# LowVBoard_02.net
KiCad netlist of a schematic drawn in EAGLE
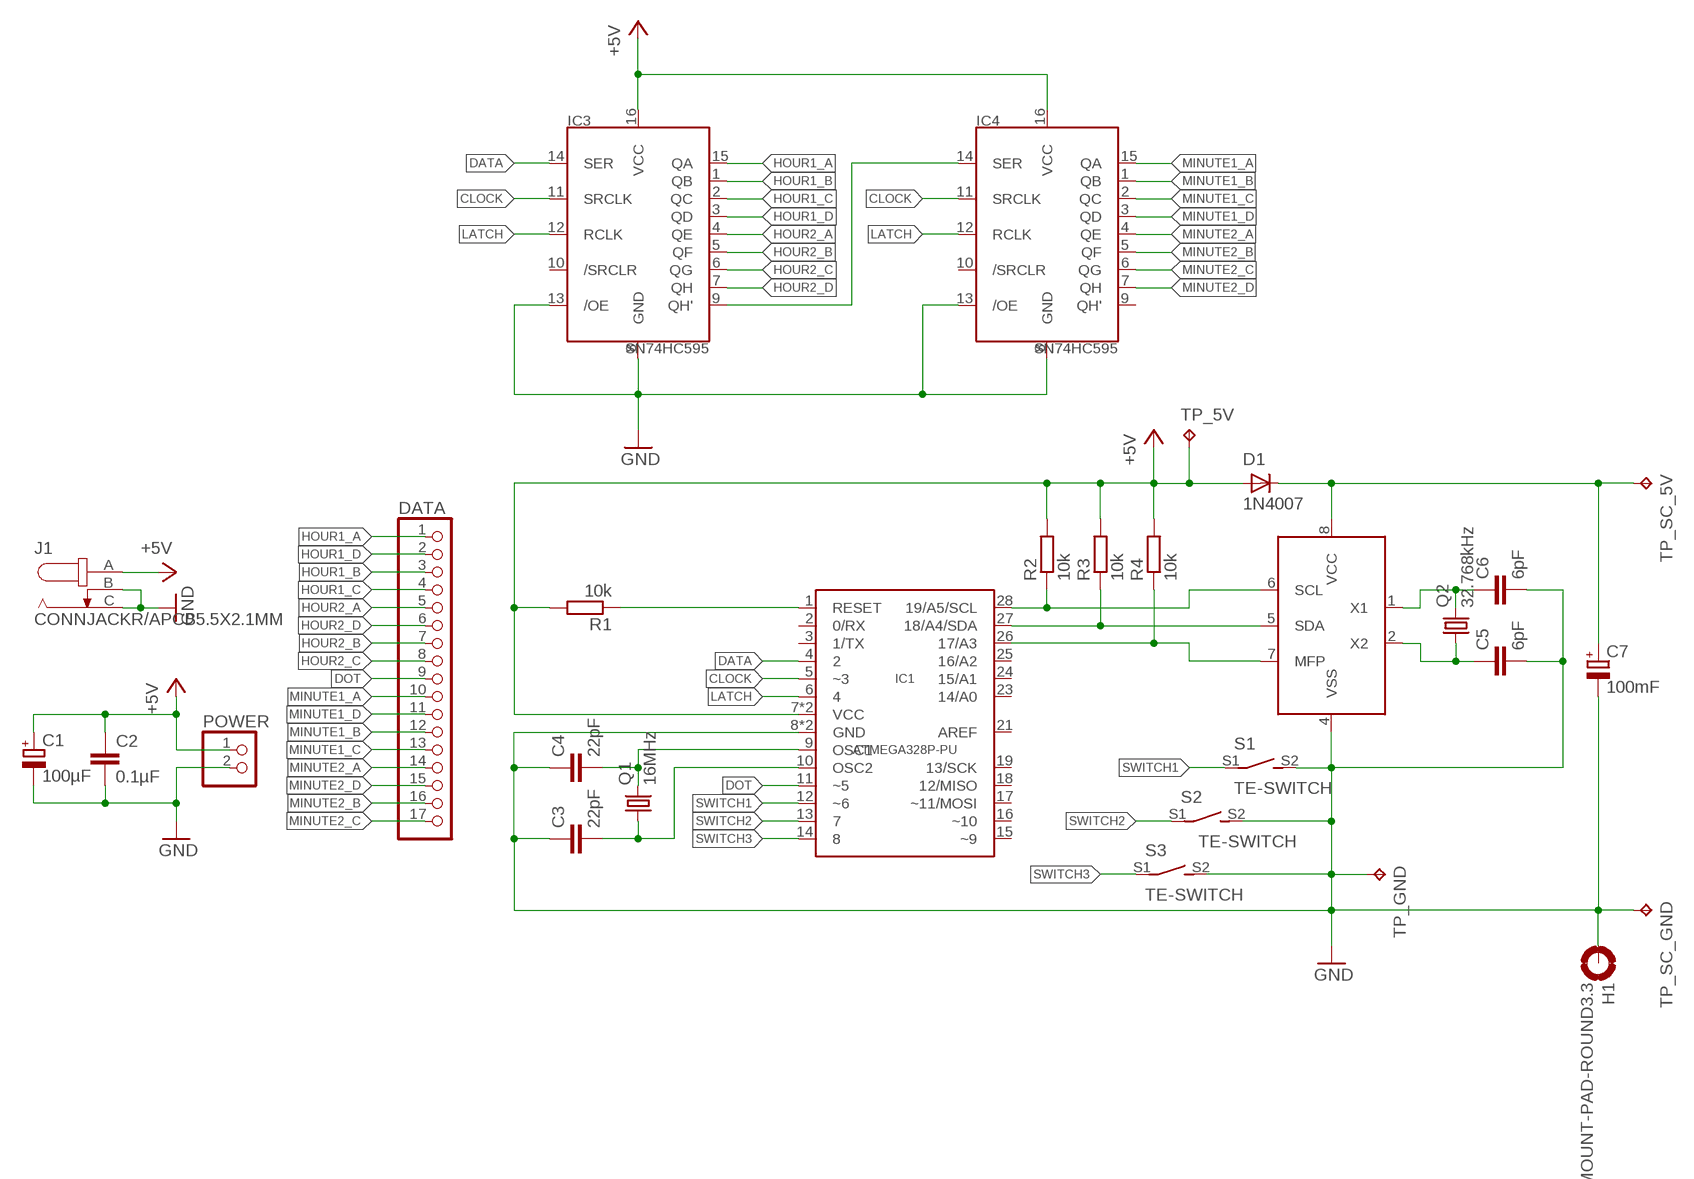
[diagram p0: schematic, sheet 1]

(export (version "E")
  (design (tool "Eeschema 10.0.6"))
  (components
    (comp (ref "C1")
      (value "100µF")
      (footprint "eagle-import:E2-5")
      (libsource (lib "eagle-import") (part "CPOL-EUE2-5"))
    )
    (comp (ref "C2")
      (value "0.1µF")
      (footprint "eagle-import:C025-024X044")
      (libsource (lib "eagle-import") (part "C-EU025-024X044"))
    )
    (comp (ref "C3")
      (value "22pF")
      (footprint "eagle-import:C025-024X044")
      (libsource (lib "eagle-import") (part "C-EU025-024X044"))
    )
    (comp (ref "C4")
      (value "22pF")
      (footprint "eagle-import:C025-024X044")
      (libsource (lib "eagle-import") (part "C-EU025-024X044"))
    )
    (comp (ref "C5")
      (value "6pF")
      (footprint "eagle-import:C025-024X044")
      (libsource (lib "eagle-import") (part "C-EU025-024X044"))
    )
    (comp (ref "C6")
      (value "6pF")
      (footprint "eagle-import:C025-024X044")
      (libsource (lib "eagle-import") (part "C-EU025-024X044"))
    )
    (comp (ref "C7")
      (value "100mF")
      (footprint "eagle-import:SUPERCAP-11.5")
      (libsource (lib "eagle-import") (part "FTW0H104ZF"))
    )
    (comp (ref "D1")
      (value "1N4007")
      (footprint "eagle-import:DO41-7.6")
      (libsource (lib "eagle-import") (part "1N4007"))
    )
    (comp (ref "DATA")
      (value "PINHD-1X17")
      (footprint "eagle-import:1X17")
      (libsource (lib "eagle-import") (part "PINHD-1X17"))
    )
    (comp (ref "H1")
      (value "MOUNT-PAD-ROUND3.3")
      (footprint "eagle-import:3,3-PAD")
      (libsource (lib "eagle-import") (part "MOUNT-PAD-ROUND3.3"))
    )
    (comp (ref "IC1")
      (value "ATMEGA328P-PU")
      (footprint "eagle-import:DIP28")
      (libsource (lib "eagle-import") (part "ATMEGA328P-PU"))
    )
    (comp (ref "IC2")
      (value "MCP7940M")
      (footprint "eagle-import:DIL8")
      (libsource (lib "eagle-import") (part "MCP7940M-I/P"))
    )
    (comp (ref "IC3")
      (value "SN74HC595")
      (footprint "eagle-import:DIL16")
      (libsource (lib "eagle-import") (part "SN74HC595"))
    )
    (comp (ref "IC4")
      (value "SN74HC595")
      (footprint "eagle-import:DIL16")
      (libsource (lib "eagle-import") (part "SN74HC595"))
    )
    (comp (ref "J1")
      (value "CONNJACKR/APCB5.5X2.1MM")
      (footprint "eagle-import:CONNJACKR_APCB5.5X2.1MM")
      (libsource (lib "eagle-import") (part "CONNJACKR/APCB5.5X2.1MM"))
    )
    (comp (ref "POWER")
      (value "PINHD-1X2")
      (footprint "eagle-import:1X02")
      (libsource (lib "eagle-import") (part "PINHD-1X2"))
    )
    (comp (ref "Q1")
      (value "16MHz")
      (footprint "eagle-import:HC49_S")
      (libsource (lib "eagle-import") (part "CRYSTALHC49S"))
    )
    (comp (ref "Q2")
      (value "32.768kHz")
      (footprint "eagle-import:CFS-206")
      (libsource (lib "eagle-import") (part "CFS-206"))
    )
    (comp (ref "R1")
      (value "10k")
      (footprint "eagle-import:0207_7")
      (libsource (lib "eagle-import") (part "R-EU_0207/7"))
    )
    (comp (ref "R2")
      (value "10k")
      (footprint "eagle-import:0207_7")
      (libsource (lib "eagle-import") (part "R-EU_0207/7"))
    )
    (comp (ref "R3")
      (value "10k")
      (footprint "eagle-import:0207_7")
      (libsource (lib "eagle-import") (part "R-EU_0207/7"))
    )
    (comp (ref "R4")
      (value "10k")
      (footprint "eagle-import:0207_7")
      (libsource (lib "eagle-import") (part "R-EU_0207/7"))
    )
    (comp (ref "S1")
      (value "TE-SWITCH")
      (footprint "eagle-import:TE-SWITCH")
      (libsource (lib "eagle-import") (part "TE-SWITCH"))
    )
    (comp (ref "S2")
      (value "TE-SWITCH")
      (footprint "eagle-import:TE-SWITCH")
      (libsource (lib "eagle-import") (part "TE-SWITCH"))
    )
    (comp (ref "S3")
      (value "TE-SWITCH")
      (footprint "eagle-import:TE-SWITCH")
      (libsource (lib "eagle-import") (part "TE-SWITCH"))
    )
    (comp (ref "TP_5V")
      (value "TPPAD1-13")
      (footprint "eagle-import:P1-13")
      (libsource (lib "eagle-import") (part "TPPAD1-13"))
    )
    (comp (ref "TP_GND")
      (value "TPPAD1-13")
      (footprint "eagle-import:P1-13")
      (libsource (lib "eagle-import") (part "TPPAD1-13"))
    )
    (comp (ref "TP_SC_5V")
      (value "TPPAD1-13")
      (footprint "eagle-import:P1-13")
      (libsource (lib "eagle-import") (part "TPPAD1-13"))
    )
    (comp (ref "TP_SC_GND")
      (value "TPPAD1-13")
      (footprint "eagle-import:P1-13")
      (libsource (lib "eagle-import") (part "TPPAD1-13"))
    )
  )
  (nets
    (net (code "1") (name "+5V") (class "Default")
      (node (ref "C1") (pin "+") (pinfunction "+_+") (pintype "passive"))
      (node (ref "C2") (pin "1") (pinfunction "1_1") (pintype "passive"))
      (node (ref "D1") (pin "A") (pinfunction "A_A") (pintype "passive"))
      (node (ref "IC1") (pin "20") (pinfunction "VCC_20") (pintype "bidirectional"))
      (node (ref "IC1") (pin "7") (pinfunction "VCC_7") (pintype "bidirectional"))
      (node (ref "IC3") (pin "16") (pinfunction "VCC_16") (pintype "bidirectional"))
      (node (ref "IC4") (pin "16") (pinfunction "VCC_16") (pintype "bidirectional"))
      (node (ref "J1") (pin "A") (pinfunction "A_A") (pintype "passive"))
      (node (ref "POWER") (pin "1") (pinfunction "1_1") (pintype "passive"))
      (node (ref "R1") (pin "2") (pinfunction "2_2") (pintype "passive"))
      (node (ref "R2") (pin "2") (pinfunction "2_2") (pintype "passive"))
      (node (ref "R3") (pin "2") (pinfunction "2_2") (pintype "passive"))
      (node (ref "R4") (pin "2") (pinfunction "2_2") (pintype "passive"))
      (node (ref "TP_5V") (pin "TP") (pinfunction "TP_TP") (pintype "input"))
    )
    (net (code "2") (name "CLOCK") (class "Default")
      (node (ref "IC1") (pin "5") (pinfunction "~{3}_5") (pintype "bidirectional"))
      (node (ref "IC3") (pin "11") (pinfunction "SRCLK_11") (pintype "bidirectional"))
      (node (ref "IC4") (pin "11") (pinfunction "SRCLK_11") (pintype "bidirectional"))
    )
    (net (code "3") (name "DATA") (class "Default")
      (node (ref "IC1") (pin "4") (pinfunction "2_4") (pintype "bidirectional"))
      (node (ref "IC3") (pin "14") (pinfunction "SER_14") (pintype "bidirectional"))
    )
    (net (code "4") (name "DOT") (class "Default")
      (node (ref "DATA") (pin "9") (pinfunction "9_9") (pintype "passive"))
      (node (ref "IC1") (pin "11") (pinfunction "~{5}_11") (pintype "bidirectional"))
    )
    (net (code "5") (name "GND") (class "Default")
      (node (ref "C1") (pin "-") (pinfunction "-_-") (pintype "passive"))
      (node (ref "C2") (pin "2") (pinfunction "2_2") (pintype "passive"))
      (node (ref "C3") (pin "1") (pinfunction "1_1") (pintype "passive"))
      (node (ref "C4") (pin "1") (pinfunction "1_1") (pintype "passive"))
      (node (ref "C5") (pin "2") (pinfunction "2_2") (pintype "passive"))
      (node (ref "C6") (pin "2") (pinfunction "2_2") (pintype "passive"))
      (node (ref "C7") (pin "-") (pinfunction "-_-") (pintype "passive"))
      (node (ref "H1") (pin "B3,3") (pinfunction "MOUNT_B3,3") (pintype "passive"))
      (node (ref "IC1") (pin "22") (pinfunction "GND_22") (pintype "bidirectional"))
      (node (ref "IC1") (pin "8") (pinfunction "GND_8") (pintype "bidirectional"))
      (node (ref "IC2") (pin "4") (pinfunction "VSS_4") (pintype "bidirectional"))
      (node (ref "IC3") (pin "13") (pinfunction "/OE_13") (pintype "bidirectional"))
      (node (ref "IC3") (pin "8") (pinfunction "GND_8") (pintype "bidirectional"))
      (node (ref "IC4") (pin "13") (pinfunction "/OE_13") (pintype "bidirectional"))
      (node (ref "IC4") (pin "8") (pinfunction "GND_8") (pintype "bidirectional"))
      (node (ref "J1") (pin "B") (pinfunction "B_B") (pintype "passive"))
      (node (ref "J1") (pin "C") (pinfunction "C_C") (pintype "passive"))
      (node (ref "POWER") (pin "2") (pinfunction "2_2") (pintype "passive"))
      (node (ref "S1") (pin "S2") (pinfunction "S_S2") (pintype "passive"))
      (node (ref "S2") (pin "S2") (pinfunction "S_S2") (pintype "passive"))
      (node (ref "S3") (pin "S2") (pinfunction "S_S2") (pintype "passive"))
      (node (ref "TP_GND") (pin "TP") (pinfunction "TP_TP") (pintype "input"))
      (node (ref "TP_SC_GND") (pin "TP") (pinfunction "TP_TP") (pintype "input"))
    )
    (net (code "6") (name "HOUR1_A") (class "Default")
      (node (ref "DATA") (pin "1") (pinfunction "1_1") (pintype "passive"))
      (node (ref "IC3") (pin "15") (pinfunction "QA_15") (pintype "bidirectional"))
    )
    (net (code "7") (name "HOUR1_B") (class "Default")
      (node (ref "DATA") (pin "3") (pinfunction "3_3") (pintype "passive"))
      (node (ref "IC3") (pin "1") (pinfunction "QB_1") (pintype "bidirectional"))
    )
    (net (code "8") (name "HOUR1_C") (class "Default")
      (node (ref "DATA") (pin "4") (pinfunction "4_4") (pintype "passive"))
      (node (ref "IC3") (pin "2") (pinfunction "QC_2") (pintype "bidirectional"))
    )
    (net (code "9") (name "HOUR1_D") (class "Default")
      (node (ref "DATA") (pin "2") (pinfunction "2_2") (pintype "passive"))
      (node (ref "IC3") (pin "3") (pinfunction "QD_3") (pintype "bidirectional"))
    )
    (net (code "10") (name "HOUR2_A") (class "Default")
      (node (ref "DATA") (pin "5") (pinfunction "5_5") (pintype "passive"))
      (node (ref "IC3") (pin "4") (pinfunction "QE_4") (pintype "bidirectional"))
    )
    (net (code "11") (name "HOUR2_B") (class "Default")
      (node (ref "DATA") (pin "7") (pinfunction "7_7") (pintype "passive"))
      (node (ref "IC3") (pin "5") (pinfunction "QF_5") (pintype "bidirectional"))
    )
    (net (code "12") (name "HOUR2_C") (class "Default")
      (node (ref "DATA") (pin "8") (pinfunction "8_8") (pintype "passive"))
      (node (ref "IC3") (pin "6") (pinfunction "QG_6") (pintype "bidirectional"))
    )
    (net (code "13") (name "HOUR2_D") (class "Default")
      (node (ref "DATA") (pin "6") (pinfunction "6_6") (pintype "passive"))
      (node (ref "IC3") (pin "7") (pinfunction "QH_7") (pintype "bidirectional"))
    )
    (net (code "14") (name "LATCH") (class "Default")
      (node (ref "IC1") (pin "6") (pinfunction "4_6") (pintype "bidirectional"))
      (node (ref "IC3") (pin "12") (pinfunction "RCLK_12") (pintype "bidirectional"))
      (node (ref "IC4") (pin "12") (pinfunction "RCLK_12") (pintype "bidirectional"))
    )
    (net (code "15") (name "MINUTE1_A") (class "Default")
      (node (ref "DATA") (pin "10") (pinfunction "10_10") (pintype "passive"))
      (node (ref "IC4") (pin "15") (pinfunction "QA_15") (pintype "bidirectional"))
    )
    (net (code "16") (name "MINUTE1_B") (class "Default")
      (node (ref "DATA") (pin "12") (pinfunction "12_12") (pintype "passive"))
      (node (ref "IC4") (pin "1") (pinfunction "QB_1") (pintype "bidirectional"))
    )
    (net (code "17") (name "MINUTE1_C") (class "Default")
      (node (ref "DATA") (pin "13") (pinfunction "13_13") (pintype "passive"))
      (node (ref "IC4") (pin "2") (pinfunction "QC_2") (pintype "bidirectional"))
    )
    (net (code "18") (name "MINUTE1_D") (class "Default")
      (node (ref "DATA") (pin "11") (pinfunction "11_11") (pintype "passive"))
      (node (ref "IC4") (pin "3") (pinfunction "QD_3") (pintype "bidirectional"))
    )
    (net (code "19") (name "MINUTE2_A") (class "Default")
      (node (ref "DATA") (pin "14") (pinfunction "14_14") (pintype "passive"))
      (node (ref "IC4") (pin "4") (pinfunction "QE_4") (pintype "bidirectional"))
    )
    (net (code "20") (name "MINUTE2_B") (class "Default")
      (node (ref "DATA") (pin "16") (pinfunction "16_16") (pintype "passive"))
      (node (ref "IC4") (pin "5") (pinfunction "QF_5") (pintype "bidirectional"))
    )
    (net (code "21") (name "MINUTE2_C") (class "Default")
      (node (ref "DATA") (pin "17") (pinfunction "17_17") (pintype "passive"))
      (node (ref "IC4") (pin "6") (pinfunction "QG_6") (pintype "bidirectional"))
    )
    (net (code "22") (name "MINUTE2_D") (class "Default")
      (node (ref "DATA") (pin "15") (pinfunction "15_15") (pintype "passive"))
      (node (ref "IC4") (pin "7") (pinfunction "QH_7") (pintype "bidirectional"))
    )
    (net (code "23") (name "Net-(IC1-17{slash}A3)") (class "Default")
      (node (ref "IC1") (pin "26") (pinfunction "17/A3_26") (pintype "bidirectional"))
      (node (ref "IC2") (pin "7") (pinfunction "MFP_7") (pintype "bidirectional"))
      (node (ref "R4") (pin "1") (pinfunction "1_1") (pintype "passive"))
    )
    (net (code "24") (name "Net-(IC1-18{slash}A4{slash}SDA)") (class "Default")
      (node (ref "IC1") (pin "27") (pinfunction "18/A4/SDA_27") (pintype "bidirectional"))
      (node (ref "IC2") (pin "5") (pinfunction "SDA_5") (pintype "bidirectional"))
      (node (ref "R3") (pin "1") (pinfunction "1_1") (pintype "passive"))
    )
    (net (code "25") (name "Net-(IC1-19{slash}A5{slash}SCL)") (class "Default")
      (node (ref "IC1") (pin "28") (pinfunction "19/A5/SCL_28") (pintype "bidirectional"))
      (node (ref "IC2") (pin "6") (pinfunction "SCL_6") (pintype "bidirectional"))
      (node (ref "R2") (pin "1") (pinfunction "1_1") (pintype "passive"))
    )
    (net (code "26") (name "Net-(IC1-OSC1)") (class "Default")
      (node (ref "C4") (pin "2") (pinfunction "2_2") (pintype "passive"))
      (node (ref "IC1") (pin "9") (pinfunction "OSC1_9") (pintype "bidirectional"))
      (node (ref "Q1") (pin "2") (pinfunction "2_2") (pintype "passive"))
    )
    (net (code "27") (name "Net-(IC1-OSC2)") (class "Default")
      (node (ref "C3") (pin "2") (pinfunction "2_2") (pintype "passive"))
      (node (ref "IC1") (pin "10") (pinfunction "OSC2_10") (pintype "bidirectional"))
      (node (ref "Q1") (pin "1") (pinfunction "1_1") (pintype "passive"))
    )
    (net (code "28") (name "Net-(IC1-RESET)") (class "Default")
      (node (ref "IC1") (pin "1") (pinfunction "RESET_1") (pintype "bidirectional"))
      (node (ref "R1") (pin "1") (pinfunction "1_1") (pintype "passive"))
    )
    (net (code "29") (name "Net-(IC2-VCC)") (class "Default")
      (node (ref "C7") (pin "+") (pinfunction "+_+") (pintype "passive"))
      (node (ref "D1") (pin "C") (pinfunction "C_C") (pintype "passive"))
      (node (ref "IC2") (pin "8") (pinfunction "VCC_8") (pintype "bidirectional"))
      (node (ref "TP_SC_5V") (pin "TP") (pinfunction "TP_TP") (pintype "input"))
    )
    (net (code "30") (name "Net-(IC2-X1)") (class "Default")
      (node (ref "C6") (pin "1") (pinfunction "1_1") (pintype "passive"))
      (node (ref "IC2") (pin "1") (pinfunction "X1_1") (pintype "bidirectional"))
      (node (ref "Q2") (pin "P$2") (pinfunction "2_P$2") (pintype "passive"))
    )
    (net (code "31") (name "Net-(IC2-X2)") (class "Default")
      (node (ref "C5") (pin "1") (pinfunction "1_1") (pintype "passive"))
      (node (ref "IC2") (pin "2") (pinfunction "X2_2") (pintype "bidirectional"))
      (node (ref "Q2") (pin "P$1") (pinfunction "1_P$1") (pintype "passive"))
    )
    (net (code "32") (name "Net-(IC3-QH')") (class "Default")
      (node (ref "IC3") (pin "9") (pinfunction "QH'_9") (pintype "bidirectional"))
      (node (ref "IC4") (pin "14") (pinfunction "SER_14") (pintype "bidirectional"))
    )
    (net (code "33") (name "SWITCH1") (class "Default")
      (node (ref "IC1") (pin "12") (pinfunction "~{6}_12") (pintype "bidirectional"))
      (node (ref "S1") (pin "S1") (pinfunction "P_S1") (pintype "passive"))
    )
    (net (code "34") (name "SWITCH2") (class "Default")
      (node (ref "IC1") (pin "13") (pinfunction "7_13") (pintype "bidirectional"))
      (node (ref "S2") (pin "S1") (pinfunction "P_S1") (pintype "passive"))
    )
    (net (code "35") (name "SWITCH3") (class "Default")
      (node (ref "IC1") (pin "14") (pinfunction "8_14") (pintype "bidirectional"))
      (node (ref "S3") (pin "S1") (pinfunction "P_S1") (pintype "passive"))
    )
    (net (code "36") (name "unconnected-(IC1-0{slash}RX-Pad2)") (class "Default")
      (node (ref "IC1") (pin "2") (pinfunction "0/RX_2") (pintype "bidirectional"))
    )
    (net (code "37") (name "unconnected-(IC1-1{slash}TX-Pad3)") (class "Default")
      (node (ref "IC1") (pin "3") (pinfunction "1/TX_3") (pintype "bidirectional"))
    )
    (net (code "38") (name "unconnected-(IC1-12{slash}MISO-Pad18)") (class "Default")
      (node (ref "IC1") (pin "18") (pinfunction "12/MISO_18") (pintype "bidirectional"))
    )
    (net (code "39") (name "unconnected-(IC1-13{slash}SCK-Pad19)") (class "Default")
      (node (ref "IC1") (pin "19") (pinfunction "13/SCK_19") (pintype "bidirectional"))
    )
    (net (code "40") (name "unconnected-(IC1-14{slash}A0-Pad23)") (class "Default")
      (node (ref "IC1") (pin "23") (pinfunction "14/A0_23") (pintype "bidirectional"))
    )
    (net (code "41") (name "unconnected-(IC1-15{slash}A1-Pad24)") (class "Default")
      (node (ref "IC1") (pin "24") (pinfunction "15/A1_24") (pintype "bidirectional"))
    )
    (net (code "42") (name "unconnected-(IC1-16{slash}A2-Pad25)") (class "Default")
      (node (ref "IC1") (pin "25") (pinfunction "16/A2_25") (pintype "bidirectional"))
    )
    (net (code "43") (name "unconnected-(IC1-AREF-Pad21)") (class "Default")
      (node (ref "IC1") (pin "21") (pinfunction "AREF_21") (pintype "bidirectional"))
    )
    (net (code "44") (name "unconnected-(IC1-~{9}-Pad15)") (class "Default")
      (node (ref "IC1") (pin "15") (pinfunction "~{9}_15") (pintype "bidirectional"))
    )
    (net (code "45") (name "unconnected-(IC1-~{10}-Pad16)") (class "Default")
      (node (ref "IC1") (pin "16") (pinfunction "~{10}_16") (pintype "bidirectional"))
    )
    (net (code "46") (name "unconnected-(IC1-~{11{slash}MOSI}-Pad17)") (class "Default")
      (node (ref "IC1") (pin "17") (pinfunction "~{11/MOSI}_17") (pintype "bidirectional"))
    )
    (net (code "47") (name "unconnected-(IC3-{slash}SRCLR-Pad10)") (class "Default")
      (node (ref "IC3") (pin "10") (pinfunction "/SRCLR_10") (pintype "bidirectional"))
    )
    (net (code "48") (name "unconnected-(IC4-QH'-Pad9)") (class "Default")
      (node (ref "IC4") (pin "9") (pinfunction "QH'_9") (pintype "bidirectional"))
    )
    (net (code "49") (name "unconnected-(IC4-{slash}SRCLR-Pad10)") (class "Default")
      (node (ref "IC4") (pin "10") (pinfunction "/SRCLR_10") (pintype "bidirectional"))
    )
  )
)
